# page1.net
KiCad netlist of a schematic drawn in EAGLE
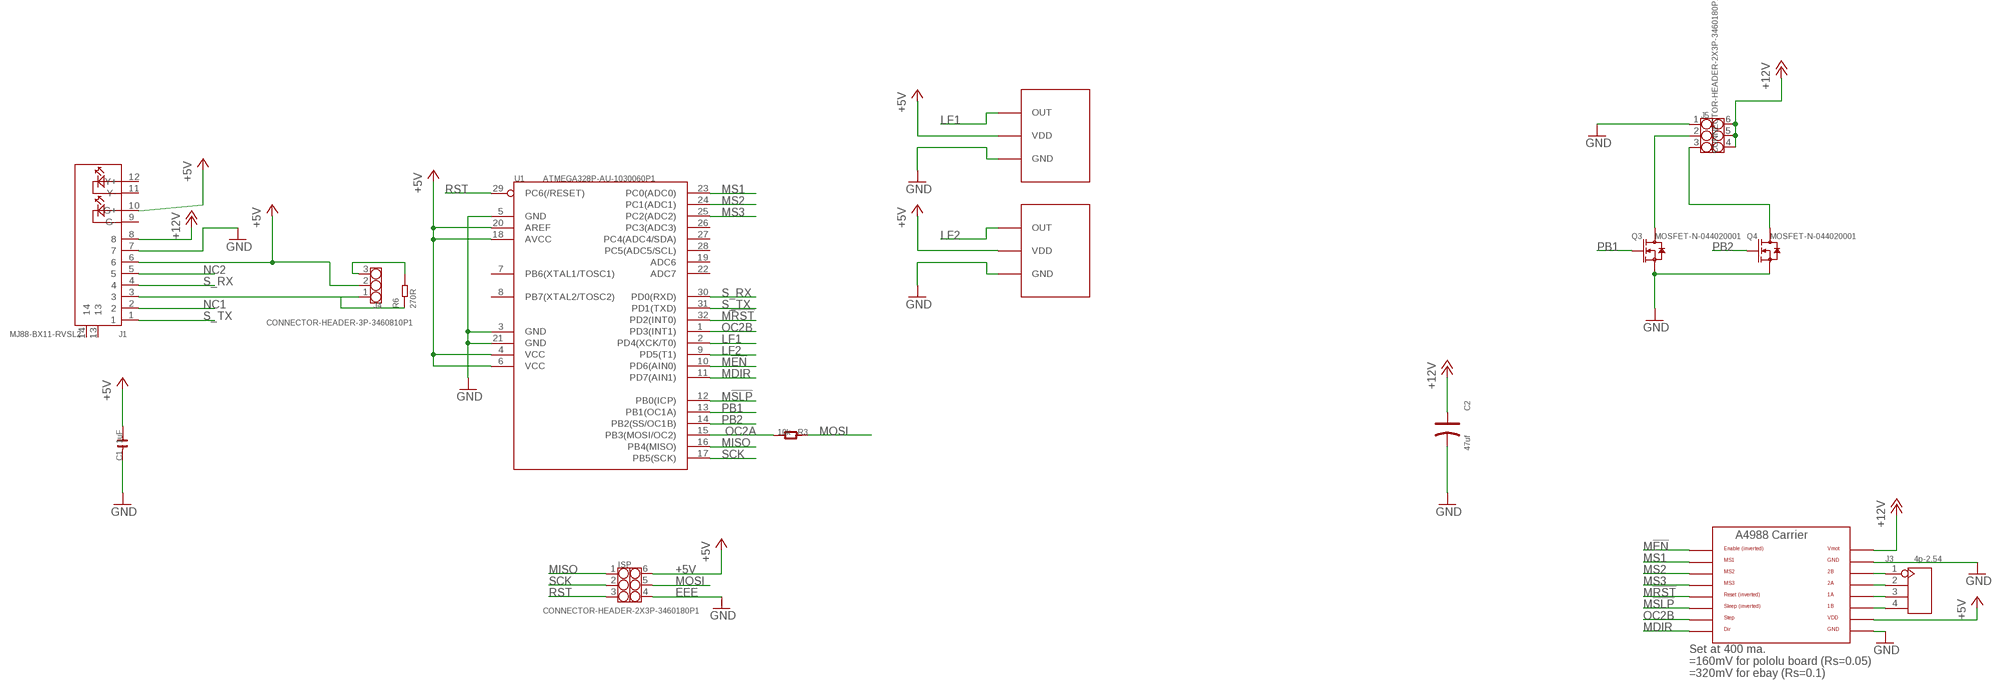
[diagram p0: schematic, sheet 1]

(export (version "E")
  (design (tool "Eeschema 10.0.6"))
  (components
    (comp (ref "C1")
      (value "1uF")
      (footprint "eagle-import:C0805")
      (libsource (lib "eagle-import") (part "C-0805"))
    )
    (comp (ref "C2")
      (value "47uf")
      (footprint "eagle-import:AVX-C")
      (fields (field (name "MPN") "TAJC476*016#NJ"))
      (libsource (lib "eagle-import") (part "TANTALUM-SMD-47UF-16V(AVX-C)"))
    )
    (comp (ref "ISP")
      (value "CONNECTOR-HEADER-2X3P-3460180P1")
      (footprint "eagle-import:2X3P-2.54-2.54-11.6-3.0-BLACK-MALE")
      (libsource (lib "eagle-import") (part "CONNECTOR-HEADER-2X3P-3460180P1"))
    )
    (comp (ref "J1")
      (value "MJ88-BX11-RVSL2")
      (footprint "eagle-import:RJ45-12+2P-16.3X15.4X11.5MM-IN")
      (libsource (lib "eagle-import") (part "RJ45-MJ88-BX11-RVSL2"))
    )
    (comp (ref "J3")
      (value "4p-2.54")
      (footprint "eagle-import:H4-2.54")
      (fields (field (name "MPN") "P125-1104A0BS116A1"))
      (libsource (lib "eagle-import") (part "DIP-BLACK-MALE-HEADER-VERT(4P-2.54)"))
    )
    (comp (ref "J4")
      (value "CONNECTOR-HEADER-3P-3460810P1")
      (footprint "eagle-import:1X3P-2.54-2.54-11.6-3.0-BLACK-MALE")
      (libsource (lib "eagle-import") (part "CONNECTOR-HEADER-3P-3460810P1"))
    )
    (comp (ref "J5")
      (value "CONNECTOR-HEADER-2X3P-3460180P1")
      (footprint "eagle-import:2X3P-2.54-2.54-11.6-3.0-BLACK-MALE")
      (libsource (lib "eagle-import") (part "CONNECTOR-HEADER-2X3P-3460180P1"))
    )
    (comp (ref "Q3")
      (value "MOSFET-N-044020001")
      (footprint "eagle-import:SOT23")
      (libsource (lib "eagle-import") (part "MOSFET-N-044020001"))
    )
    (comp (ref "Q4")
      (value "MOSFET-N-044020001")
      (footprint "eagle-import:SOT23")
      (libsource (lib "eagle-import") (part "MOSFET-N-044020001"))
    )
    (comp (ref "R3")
      (value "10k")
      (footprint "eagle-import:R0603")
      (libsource (lib "eagle-import") (part "R-0603"))
    )
    (comp (ref "R6")
      (value "270R")
      (footprint "eagle-import:R0805")
      (fields (field (name "MPN") "RC0805JR-07270RL"))
      (libsource (lib "eagle-import") (part "SMD-RES-270R-5%-1/8W(0805)"))
    )
    (comp (ref "U$1")
      (value "A4988BREAKOUT")
      (footprint "eagle-import:A4988BREAKOUT")
      (libsource (lib "eagle-import") (part "A4988BREAKOUT"))
    )
    (comp (ref "U$5")
      (value "TSL235")
      (footprint "eagle-import:TSL235R-2MM-S")
      (libsource (lib "eagle-import") (part "TSL235"))
    )
    (comp (ref "U$6")
      (value "TSL235")
      (footprint "eagle-import:TSL235R-2MM-S")
      (libsource (lib "eagle-import") (part "TSL235"))
    )
    (comp (ref "U1")
      (value "ATMEGA328P-AU-1030060P1")
      (footprint "eagle-import:TQFP32")
      (libsource (lib "eagle-import") (part "ATMEGA328P-AU-1030060P1"))
    )
  )
  (nets
    (net (code "1") (name "+5V") (class "Default")
      (node (ref "C1") (pin "2") (pinfunction "2_2") (pintype "bidirectional"))
      (node (ref "ISP") (pin "6") (pinfunction "6_6") (pintype "bidirectional"))
      (node (ref "J1") (pin "10") (pinfunction "G+_10") (pintype "bidirectional"))
      (node (ref "J1") (pin "6") (pinfunction "6_6") (pintype "bidirectional"))
      (node (ref "J4") (pin "2") (pinfunction "2_2") (pintype "bidirectional"))
      (node (ref "U$1") (pin "VDD") (pinfunction "VDD_VDD") (pintype "power_in"))
      (node (ref "U$5") (pin "P$2") (pinfunction "VDD_P$2") (pintype "bidirectional"))
      (node (ref "U$6") (pin "P$2") (pinfunction "VDD_P$2") (pintype "bidirectional"))
      (node (ref "U1") (pin "18") (pinfunction "AVCC_18") (pintype "bidirectional"))
      (node (ref "U1") (pin "20") (pinfunction "AREF_20") (pintype "bidirectional"))
      (node (ref "U1") (pin "4") (pinfunction "VCC_4") (pintype "bidirectional"))
      (node (ref "U1") (pin "6") (pinfunction "VCC_6") (pintype "bidirectional"))
    )
    (net (code "2") (name "+12V") (class "Default")
      (node (ref "C2") (pin "+") (pinfunction "+_+") (pintype "passive"))
      (node (ref "J1") (pin "8") (pinfunction "8_8") (pintype "bidirectional"))
      (node (ref "J5") (pin "4") (pinfunction "4_4") (pintype "bidirectional"))
      (node (ref "J5") (pin "5") (pinfunction "5_5") (pintype "bidirectional"))
      (node (ref "J5") (pin "6") (pinfunction "6_6") (pintype "bidirectional"))
      (node (ref "U$1") (pin "VMOT") (pinfunction "VMOT_VMOT") (pintype "power_in"))
    )
    (net (code "3") (name "/LF1") (class "Default")
      (node (ref "U$5") (pin "P$3") (pinfunction "OUT_P$3") (pintype "output"))
      (node (ref "U1") (pin "2") (pinfunction "PD4(XCK/T0)_2") (pintype "bidirectional"))
    )
    (net (code "4") (name "/LF2") (class "Default")
      (node (ref "U$6") (pin "P$3") (pinfunction "OUT_P$3") (pintype "output"))
      (node (ref "U1") (pin "9") (pinfunction "PD5(T1)_9") (pintype "bidirectional"))
    )
    (net (code "5") (name "/MDIR") (class "Default")
      (node (ref "U$1") (pin "DIR") (pinfunction "DIR_DIR") (pintype "input"))
      (node (ref "U1") (pin "11") (pinfunction "PD7(AIN1)_11") (pintype "bidirectional"))
    )
    (net (code "6") (name "/MISO") (class "Default")
      (node (ref "ISP") (pin "1") (pinfunction "1_1") (pintype "bidirectional"))
      (node (ref "U1") (pin "16") (pinfunction "PB4(MISO)_16") (pintype "bidirectional"))
    )
    (net (code "7") (name "/MOSI") (class "Default")
      (node (ref "ISP") (pin "5") (pinfunction "5_5") (pintype "bidirectional"))
      (node (ref "R3") (pin "1") (pinfunction "1_1") (pintype "bidirectional"))
    )
    (net (code "8") (name "/MS1") (class "Default")
      (node (ref "U$1") (pin "MS1") (pinfunction "MS1_MS1") (pintype "input"))
      (node (ref "U1") (pin "23") (pinfunction "PC0(ADC0)_23") (pintype "bidirectional"))
    )
    (net (code "9") (name "/MS2") (class "Default")
      (node (ref "U$1") (pin "MS2") (pinfunction "MS2_MS2") (pintype "input"))
      (node (ref "U1") (pin "24") (pinfunction "PC1(ADC1)_24") (pintype "bidirectional"))
    )
    (net (code "10") (name "/MS3") (class "Default")
      (node (ref "U$1") (pin "MS3") (pinfunction "MS3_MS3") (pintype "input"))
      (node (ref "U1") (pin "25") (pinfunction "PC2(ADC2)_25") (pintype "bidirectional"))
    )
    (net (code "11") (name "/M~{EN}") (class "Default")
      (node (ref "U$1") (pin "EN") (pinfunction "EN_EN") (pintype "input"))
      (node (ref "U1") (pin "10") (pinfunction "PD6(AIN0)_10") (pintype "bidirectional"))
    )
    (net (code "12") (name "/M~{RST}") (class "Default")
      (node (ref "U$1") (pin "RST") (pinfunction "RST_RST") (pintype "input"))
      (node (ref "U1") (pin "32") (pinfunction "PD2(INT0)_32") (pintype "bidirectional"))
    )
    (net (code "13") (name "/M~{SLP}") (class "Default")
      (node (ref "U$1") (pin "SLP") (pinfunction "SLEEP_SLP") (pintype "input"))
      (node (ref "U1") (pin "12") (pinfunction "PB0(ICP)_12") (pintype "bidirectional"))
    )
    (net (code "14") (name "/NC1") (class "Default")
      (node (ref "J1") (pin "2") (pinfunction "2_2") (pintype "bidirectional"))
    )
    (net (code "15") (name "/NC2") (class "Default")
      (node (ref "J1") (pin "5") (pinfunction "5_5") (pintype "bidirectional"))
    )
    (net (code "16") (name "/OC2A") (class "Default")
      (node (ref "R3") (pin "2") (pinfunction "2_2") (pintype "bidirectional"))
      (node (ref "U1") (pin "15") (pinfunction "PB3(MOSI/OC2)_15") (pintype "bidirectional"))
    )
    (net (code "17") (name "/OC2B") (class "Default")
      (node (ref "U$1") (pin "STEP") (pinfunction "STEP_STEP") (pintype "input"))
      (node (ref "U1") (pin "1") (pinfunction "PD3(INT1)_1") (pintype "bidirectional"))
    )
    (net (code "18") (name "/PB1") (class "Default")
      (node (ref "Q3") (pin "1") (pinfunction "G_1") (pintype "passive"))
      (node (ref "U1") (pin "13") (pinfunction "PB1(OC1A)_13") (pintype "bidirectional"))
    )
    (net (code "19") (name "/PB2") (class "Default")
      (node (ref "Q4") (pin "1") (pinfunction "G_1") (pintype "passive"))
      (node (ref "U1") (pin "14") (pinfunction "PB2(SS/OC1B)_14") (pintype "bidirectional"))
    )
    (net (code "20") (name "/RST") (class "Default")
      (node (ref "ISP") (pin "3") (pinfunction "3_3") (pintype "bidirectional"))
      (node (ref "U1") (pin "29") (pinfunction "PC6(/RESET)_29") (pintype "bidirectional"))
    )
    (net (code "21") (name "/SCK") (class "Default")
      (node (ref "ISP") (pin "2") (pinfunction "2_2") (pintype "bidirectional"))
      (node (ref "U1") (pin "17") (pinfunction "PB5(SCK)_17") (pintype "bidirectional"))
    )
    (net (code "22") (name "/S_RX") (class "Default")
      (node (ref "J1") (pin "4") (pinfunction "4_4") (pintype "bidirectional"))
      (node (ref "U1") (pin "30") (pinfunction "PD0(RXD)_30") (pintype "bidirectional"))
    )
    (net (code "23") (name "/S_TX") (class "Default")
      (node (ref "J1") (pin "1") (pinfunction "1_1") (pintype "bidirectional"))
      (node (ref "U1") (pin "31") (pinfunction "PD1(TXD)_31") (pintype "bidirectional"))
    )
    (net (code "24") (name "GND") (class "Default")
      (node (ref "C1") (pin "1") (pinfunction "1_1") (pintype "bidirectional"))
      (node (ref "C2") (pin "-") (pinfunction "-_-") (pintype "passive"))
      (node (ref "ISP") (pin "4") (pinfunction "4_4") (pintype "bidirectional"))
      (node (ref "J1") (pin "7") (pinfunction "7_7") (pintype "bidirectional"))
      (node (ref "J5") (pin "1") (pinfunction "1_1") (pintype "bidirectional"))
      (node (ref "Q3") (pin "2") (pinfunction "S_2") (pintype "passive"))
      (node (ref "Q4") (pin "2") (pinfunction "S_2") (pintype "passive"))
      (node (ref "U$1") (pin "GND") (pinfunction "GND_GND") (pintype "power_in"))
      (node (ref "U$1") (pin "GND@0") (pinfunction "GND_GND@0") (pintype "power_in"))
      (node (ref "U$5") (pin "P$1") (pinfunction "GND_P$1") (pintype "bidirectional"))
      (node (ref "U$6") (pin "P$1") (pinfunction "GND_P$1") (pintype "bidirectional"))
      (node (ref "U1") (pin "21") (pinfunction "GND_21") (pintype "bidirectional"))
      (node (ref "U1") (pin "3") (pinfunction "GND_3") (pintype "bidirectional"))
      (node (ref "U1") (pin "5") (pinfunction "GND_5") (pintype "bidirectional"))
    )
    (net (code "25") (name "Net-(J1-Pad3)") (class "Default")
      (node (ref "J1") (pin "3") (pinfunction "3_3") (pintype "bidirectional"))
      (node (ref "J4") (pin "1") (pinfunction "1_1") (pintype "bidirectional"))
      (node (ref "R6") (pin "1") (pinfunction "1_1") (pintype "passive"))
    )
    (net (code "26") (name "Net-(J3-P$1)") (class "Default")
      (node (ref "J3") (pin "1") (pinfunction "P$1_1") (pintype "bidirectional"))
      (node (ref "U$1") (pin "2B") (pinfunction "2B_2B") (pintype "output"))
    )
    (net (code "27") (name "Net-(J3-P$2)") (class "Default")
      (node (ref "J3") (pin "2") (pinfunction "P$2_2") (pintype "bidirectional"))
      (node (ref "U$1") (pin "2A") (pinfunction "2A_2A") (pintype "output"))
    )
    (net (code "28") (name "Net-(J3-P$3)") (class "Default")
      (node (ref "J3") (pin "3") (pinfunction "P$3_3") (pintype "bidirectional"))
      (node (ref "U$1") (pin "1A") (pinfunction "1A_1A") (pintype "output"))
    )
    (net (code "29") (name "Net-(J3-P$4)") (class "Default")
      (node (ref "J3") (pin "4") (pinfunction "P$4_4") (pintype "bidirectional"))
      (node (ref "U$1") (pin "1B") (pinfunction "1B_1B") (pintype "output"))
    )
    (net (code "30") (name "Net-(J4-Pad3)") (class "Default")
      (node (ref "J4") (pin "3") (pinfunction "3_3") (pintype "bidirectional"))
      (node (ref "R6") (pin "2") (pinfunction "2_2") (pintype "passive"))
    )
    (net (code "31") (name "Net-(Q3-D)") (class "Default")
      (node (ref "J5") (pin "2") (pinfunction "2_2") (pintype "bidirectional"))
      (node (ref "Q3") (pin "3") (pinfunction "D_3") (pintype "passive"))
    )
    (net (code "32") (name "Net-(Q4-D)") (class "Default")
      (node (ref "J5") (pin "3") (pinfunction "3_3") (pintype "bidirectional"))
      (node (ref "Q4") (pin "3") (pinfunction "D_3") (pintype "passive"))
    )
    (net (code "33") (name "unconnected-(J1-G--Pad9)") (class "Default")
      (node (ref "J1") (pin "9") (pinfunction "G-_9") (pintype "bidirectional"))
    )
    (net (code "34") (name "unconnected-(J1-Pad13)") (class "Default")
      (node (ref "J1") (pin "13") (pinfunction "13_13") (pintype "bidirectional"))
    )
    (net (code "35") (name "unconnected-(J1-Pad14)") (class "Default")
      (node (ref "J1") (pin "14") (pinfunction "14_14") (pintype "bidirectional"))
    )
    (net (code "36") (name "unconnected-(J1-Y+-Pad12)") (class "Default")
      (node (ref "J1") (pin "12") (pinfunction "Y+_12") (pintype "bidirectional"))
    )
    (net (code "37") (name "unconnected-(J1-Y--Pad11)") (class "Default")
      (node (ref "J1") (pin "11") (pinfunction "Y-_11") (pintype "bidirectional"))
    )
    (net (code "38") (name "unconnected-(U1-ADC6-Pad19)") (class "Default")
      (node (ref "U1") (pin "19") (pinfunction "ADC6_19") (pintype "bidirectional"))
    )
    (net (code "39") (name "unconnected-(U1-ADC7-Pad22)") (class "Default")
      (node (ref "U1") (pin "22") (pinfunction "ADC7_22") (pintype "bidirectional"))
    )
    (net (code "40") (name "unconnected-(U1-PB6(XTAL1{slash}TOSC1)-Pad7)") (class "Default")
      (node (ref "U1") (pin "7") (pinfunction "PB6(XTAL1/TOSC1)_7") (pintype "bidirectional"))
    )
    (net (code "41") (name "unconnected-(U1-PB7(XTAL2{slash}TOSC2)-Pad8)") (class "Default")
      (node (ref "U1") (pin "8") (pinfunction "PB7(XTAL2/TOSC2)_8") (pintype "bidirectional"))
    )
    (net (code "42") (name "unconnected-(U1-PC3(ADC3)-Pad26)") (class "Default")
      (node (ref "U1") (pin "26") (pinfunction "PC3(ADC3)_26") (pintype "bidirectional"))
    )
    (net (code "43") (name "unconnected-(U1-PC4(ADC4{slash}SDA)-Pad27)") (class "Default")
      (node (ref "U1") (pin "27") (pinfunction "PC4(ADC4/SDA)_27") (pintype "bidirectional"))
    )
    (net (code "44") (name "unconnected-(U1-PC5(ADC5{slash}SCL)-Pad28)") (class "Default")
      (node (ref "U1") (pin "28") (pinfunction "PC5(ADC5/SCL)_28") (pintype "bidirectional"))
    )
  )
)
